# bancada_pitot.net
KiCad netlist of a schematic drawn in EAGLE
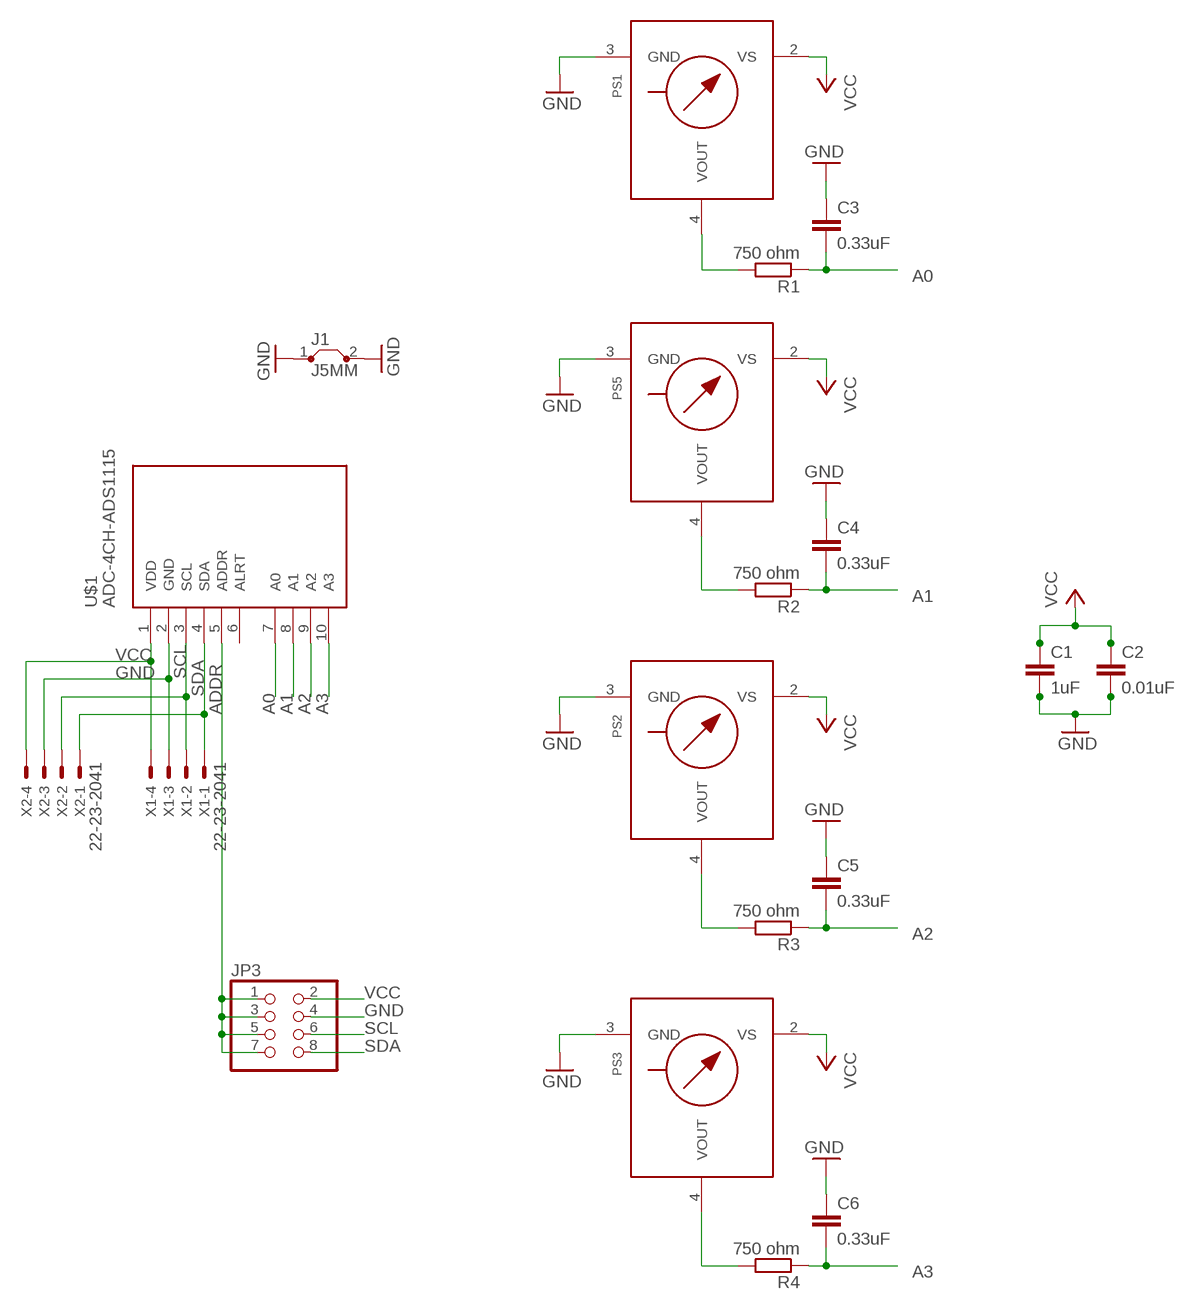
[diagram p0: schematic, sheet 1]

(export (version "E")
  (design (tool "Eeschema 10.0.6"))
  (components
    (comp (ref "C1")
      (value "1uF")
      (footprint "eagle-import:C025-025X050")
      (libsource (lib "eagle-import") (part "C-EU025-025X050"))
    )
    (comp (ref "C2")
      (value "0.01uF")
      (footprint "eagle-import:C025-025X050")
      (libsource (lib "eagle-import") (part "C-EU025-025X050"))
    )
    (comp (ref "C3")
      (value "0.33uF")
      (footprint "eagle-import:C025-025X050")
      (libsource (lib "eagle-import") (part "C-EU025-025X050"))
    )
    (comp (ref "C4")
      (value "0.33uF")
      (footprint "eagle-import:C025-025X050")
      (libsource (lib "eagle-import") (part "C-EU025-025X050"))
    )
    (comp (ref "C5")
      (value "0.33uF")
      (footprint "eagle-import:C025-025X050")
      (libsource (lib "eagle-import") (part "C-EU025-025X050"))
    )
    (comp (ref "C6")
      (value "0.33uF")
      (footprint "eagle-import:C025-025X050")
      (libsource (lib "eagle-import") (part "C-EU025-025X050"))
    )
    (comp (ref "J1")
      (value "J5MM")
      (footprint "eagle-import:05")
      (libsource (lib "eagle-import") (part "J5MM"))
    )
    (comp (ref "JP3")
      (value "PINHD-2X4")
      (footprint "eagle-import:2X04")
      (libsource (lib "eagle-import") (part "PINHD-2X4"))
    )
    (comp (ref "PS1")
      (value "MPX-1351")
      (footprint "eagle-import:1351")
      (libsource (lib "eagle-import") (part "MPX-1351"))
    )
    (comp (ref "PS2")
      (value "MPX-1351")
      (footprint "eagle-import:1351")
      (libsource (lib "eagle-import") (part "MPX-1351"))
    )
    (comp (ref "PS3")
      (value "MPX-1351")
      (footprint "eagle-import:1351")
      (libsource (lib "eagle-import") (part "MPX-1351"))
    )
    (comp (ref "PS5")
      (value "MPX-1351")
      (footprint "eagle-import:1351")
      (libsource (lib "eagle-import") (part "MPX-1351"))
    )
    (comp (ref "R1")
      (value "750 ohm")
      (footprint "eagle-import:0207_2V")
      (libsource (lib "eagle-import") (part "R-EU_0207/2V"))
    )
    (comp (ref "R2")
      (value "750 ohm")
      (footprint "eagle-import:0207_2V")
      (libsource (lib "eagle-import") (part "R-EU_0207/2V"))
    )
    (comp (ref "R3")
      (value "750 ohm")
      (footprint "eagle-import:0207_2V")
      (libsource (lib "eagle-import") (part "R-EU_0207/2V"))
    )
    (comp (ref "R4")
      (value "750 ohm")
      (footprint "eagle-import:0207_2V")
      (libsource (lib "eagle-import") (part "R-EU_0207/2V"))
    )
    (comp (ref "U$1")
      (value "ADC-4CH-ADS1115")
      (footprint "eagle-import:ADC-4CH-ADS1115")
      (libsource (lib "eagle-import") (part "ADC-4CH-ADS1115"))
    )
    (comp (ref "X1")
      (value "22-23-2041")
      (footprint "eagle-import:22-23-2041")
      (fields (field (name "MF") "MOLEX"))
      (libsource (lib "eagle-import") (part "22-23-2041"))
    )
    (comp (ref "X2")
      (value "22-23-2041")
      (footprint "eagle-import:22-23-2041")
      (fields (field (name "MF") "MOLEX"))
      (libsource (lib "eagle-import") (part "22-23-2041"))
    )
  )
  (nets
    (net (code "1") (name "/A0") (class "Default")
      (node (ref "C3") (pin "2") (pinfunction "2_2") (pintype "passive"))
      (node (ref "R1") (pin "1") (pinfunction "1_1") (pintype "passive"))
      (node (ref "U$1") (pin "7") (pinfunction "A0_7") (pintype "input"))
    )
    (net (code "2") (name "/A1") (class "Default")
      (node (ref "C4") (pin "2") (pinfunction "2_2") (pintype "passive"))
      (node (ref "R2") (pin "1") (pinfunction "1_1") (pintype "passive"))
      (node (ref "U$1") (pin "8") (pinfunction "A1_8") (pintype "input"))
    )
    (net (code "3") (name "/A2") (class "Default")
      (node (ref "C5") (pin "2") (pinfunction "2_2") (pintype "passive"))
      (node (ref "R3") (pin "1") (pinfunction "1_1") (pintype "passive"))
      (node (ref "U$1") (pin "9") (pinfunction "A2_9") (pintype "input"))
    )
    (net (code "4") (name "/A3") (class "Default")
      (node (ref "C6") (pin "2") (pinfunction "2_2") (pintype "passive"))
      (node (ref "R4") (pin "1") (pinfunction "1_1") (pintype "passive"))
      (node (ref "U$1") (pin "10") (pinfunction "A3_10") (pintype "input"))
    )
    (net (code "5") (name "/ADDR") (class "Default")
      (node (ref "JP3") (pin "1") (pinfunction "1_1") (pintype "passive"))
      (node (ref "JP3") (pin "3") (pinfunction "3_3") (pintype "passive"))
      (node (ref "JP3") (pin "5") (pinfunction "5_5") (pintype "passive"))
      (node (ref "JP3") (pin "7") (pinfunction "7_7") (pintype "passive"))
      (node (ref "U$1") (pin "5") (pinfunction "ADDR_5") (pintype "bidirectional"))
    )
    (net (code "6") (name "/SCL") (class "Default")
      (node (ref "JP3") (pin "6") (pinfunction "6_6") (pintype "passive"))
      (node (ref "U$1") (pin "3") (pinfunction "SCL_3") (pintype "bidirectional"))
      (node (ref "X1") (pin "2") (pinfunction "S_2") (pintype "passive"))
      (node (ref "X2") (pin "2") (pinfunction "S_2") (pintype "passive"))
    )
    (net (code "7") (name "/SDA") (class "Default")
      (node (ref "JP3") (pin "8") (pinfunction "8_8") (pintype "passive"))
      (node (ref "U$1") (pin "4") (pinfunction "SDA_4") (pintype "bidirectional"))
      (node (ref "X1") (pin "1") (pinfunction "S_1") (pintype "passive"))
      (node (ref "X2") (pin "1") (pinfunction "S_1") (pintype "passive"))
    )
    (net (code "8") (name "GND") (class "Default")
      (node (ref "C1") (pin "2") (pinfunction "2_2") (pintype "passive"))
      (node (ref "C2") (pin "2") (pinfunction "2_2") (pintype "passive"))
      (node (ref "C3") (pin "1") (pinfunction "1_1") (pintype "passive"))
      (node (ref "C4") (pin "1") (pinfunction "1_1") (pintype "passive"))
      (node (ref "C5") (pin "1") (pinfunction "1_1") (pintype "passive"))
      (node (ref "C6") (pin "1") (pinfunction "1_1") (pintype "passive"))
      (node (ref "J1") (pin "1") (pinfunction "1_1") (pintype "passive"))
      (node (ref "J1") (pin "2") (pinfunction "2_2") (pintype "passive"))
      (node (ref "JP3") (pin "4") (pinfunction "4_4") (pintype "passive"))
      (node (ref "PS1") (pin "3") (pinfunction "GND_3") (pintype "power_in"))
      (node (ref "PS2") (pin "3") (pinfunction "GND_3") (pintype "power_in"))
      (node (ref "PS3") (pin "3") (pinfunction "GND_3") (pintype "power_in"))
      (node (ref "PS5") (pin "3") (pinfunction "GND_3") (pintype "power_in"))
      (node (ref "U$1") (pin "2") (pinfunction "GND_2") (pintype "power_in"))
      (node (ref "X1") (pin "3") (pinfunction "S_3") (pintype "passive"))
      (node (ref "X2") (pin "3") (pinfunction "S_3") (pintype "passive"))
    )
    (net (code "9") (name "Net-(PS1-VOUT)") (class "Default")
      (node (ref "PS1") (pin "4") (pinfunction "VOUT_4") (pintype "output"))
      (node (ref "R1") (pin "2") (pinfunction "2_2") (pintype "passive"))
    )
    (net (code "10") (name "Net-(PS2-VOUT)") (class "Default")
      (node (ref "PS2") (pin "4") (pinfunction "VOUT_4") (pintype "output"))
      (node (ref "R3") (pin "2") (pinfunction "2_2") (pintype "passive"))
    )
    (net (code "11") (name "Net-(PS3-VOUT)") (class "Default")
      (node (ref "PS3") (pin "4") (pinfunction "VOUT_4") (pintype "output"))
      (node (ref "R4") (pin "2") (pinfunction "2_2") (pintype "passive"))
    )
    (net (code "12") (name "Net-(PS5-VOUT)") (class "Default")
      (node (ref "PS5") (pin "4") (pinfunction "VOUT_4") (pintype "output"))
      (node (ref "R2") (pin "2") (pinfunction "2_2") (pintype "passive"))
    )
    (net (code "13") (name "VCC") (class "Default")
      (node (ref "C1") (pin "1") (pinfunction "1_1") (pintype "passive"))
      (node (ref "C2") (pin "1") (pinfunction "1_1") (pintype "passive"))
      (node (ref "JP3") (pin "2") (pinfunction "2_2") (pintype "passive"))
      (node (ref "PS1") (pin "2") (pinfunction "VS_2") (pintype "power_in"))
      (node (ref "PS2") (pin "2") (pinfunction "VS_2") (pintype "power_in"))
      (node (ref "PS3") (pin "2") (pinfunction "VS_2") (pintype "power_in"))
      (node (ref "PS5") (pin "2") (pinfunction "VS_2") (pintype "power_in"))
      (node (ref "U$1") (pin "1") (pinfunction "VDD_1") (pintype "power_in"))
      (node (ref "X1") (pin "4") (pinfunction "S_4") (pintype "passive"))
      (node (ref "X2") (pin "4") (pinfunction "S_4") (pintype "passive"))
    )
    (net (code "14") (name "unconnected-(PS1-NC-Pad1)") (class "Default")
      (node (ref "PS1") (pin "1") (pinfunction "NC_1") (pintype "no_connect"))
    )
    (net (code "15") (name "unconnected-(PS1-NC-Pad5)") (class "Default")
      (node (ref "PS1") (pin "5") (pinfunction "NC_5") (pintype "no_connect"))
    )
    (net (code "16") (name "unconnected-(PS1-NC-Pad6)") (class "Default")
      (node (ref "PS1") (pin "6") (pinfunction "NC_6") (pintype "no_connect"))
    )
    (net (code "17") (name "unconnected-(PS2-NC-Pad1)") (class "Default")
      (node (ref "PS2") (pin "1") (pinfunction "NC_1") (pintype "no_connect"))
    )
    (net (code "18") (name "unconnected-(PS2-NC-Pad5)") (class "Default")
      (node (ref "PS2") (pin "5") (pinfunction "NC_5") (pintype "no_connect"))
    )
    (net (code "19") (name "unconnected-(PS2-NC-Pad6)") (class "Default")
      (node (ref "PS2") (pin "6") (pinfunction "NC_6") (pintype "no_connect"))
    )
    (net (code "20") (name "unconnected-(PS3-NC-Pad1)") (class "Default")
      (node (ref "PS3") (pin "1") (pinfunction "NC_1") (pintype "no_connect"))
    )
    (net (code "21") (name "unconnected-(PS3-NC-Pad5)") (class "Default")
      (node (ref "PS3") (pin "5") (pinfunction "NC_5") (pintype "no_connect"))
    )
    (net (code "22") (name "unconnected-(PS3-NC-Pad6)") (class "Default")
      (node (ref "PS3") (pin "6") (pinfunction "NC_6") (pintype "no_connect"))
    )
    (net (code "23") (name "unconnected-(PS5-NC-Pad1)") (class "Default")
      (node (ref "PS5") (pin "1") (pinfunction "NC_1") (pintype "no_connect"))
    )
    (net (code "24") (name "unconnected-(PS5-NC-Pad5)") (class "Default")
      (node (ref "PS5") (pin "5") (pinfunction "NC_5") (pintype "no_connect"))
    )
    (net (code "25") (name "unconnected-(PS5-NC-Pad6)") (class "Default")
      (node (ref "PS5") (pin "6") (pinfunction "NC_6") (pintype "no_connect"))
    )
    (net (code "26") (name "unconnected-(U$1-ALRT-Pad6)") (class "Default")
      (node (ref "U$1") (pin "6") (pinfunction "ALRT_6") (pintype "bidirectional"))
    )
  )
)
